# Connections.net
KiCad netlist of a schematic drawn in Altium Designer
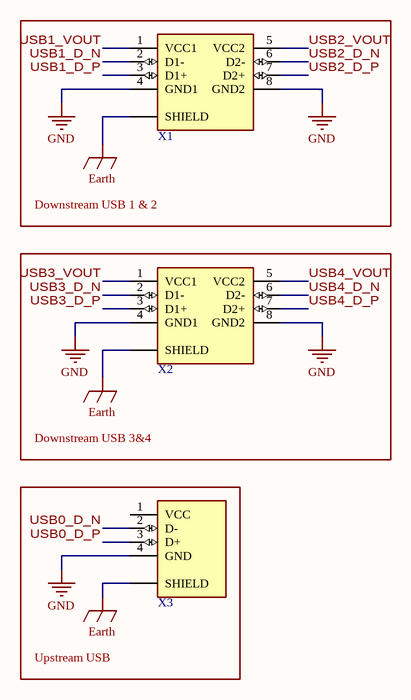
[diagram p0: Connections.SchDoc]

(export (version "E")
  (design (tool "Eeschema 10.0.6"))
  (components
    (comp (ref "X1")
      (value "USB-A")
      (footprint "[USB] Type-A Dual")
      (description "61400826021")
      (libsource (lib "Connectors") (part "[USB] Type-A Dual"))
    )
    (comp (ref "X2")
      (value "USB-A")
      (footprint "[USB] Type-A Dual")
      (description "61400826021")
      (libsource (lib "Connectors") (part "[USB] Type-A Dual"))
    )
    (comp (ref "X3")
      (value "USB-B")
      (footprint "[USB] Type-B")
      (description "USB-B-S-F-B-TH")
      (libsource (lib "Connectors") (part "[USB] Type-B"))
    )
  )
  (nets
    (net (code "1") (name "/USB0_D_N") (class "Default")
      (node (ref "X3") (pin "2") (pinfunction "D-_2") (pintype "bidirectional"))
    )
    (net (code "2") (name "/USB0_D_P") (class "Default")
      (node (ref "X3") (pin "3") (pinfunction "D+_3") (pintype "bidirectional"))
    )
    (net (code "3") (name "/USB1_D_N") (class "Default")
      (node (ref "X1") (pin "2") (pinfunction "D1-_2") (pintype "bidirectional"))
    )
    (net (code "4") (name "/USB1_D_P") (class "Default")
      (node (ref "X1") (pin "3") (pinfunction "D1+_3") (pintype "bidirectional"))
    )
    (net (code "5") (name "/USB1_VOUT") (class "Default")
      (node (ref "X1") (pin "1") (pinfunction "VCC1_1") (pintype "power_in"))
    )
    (net (code "6") (name "/USB2_D_N") (class "Default")
      (node (ref "X1") (pin "6") (pinfunction "D2-_6") (pintype "bidirectional"))
    )
    (net (code "7") (name "/USB2_D_P") (class "Default")
      (node (ref "X1") (pin "7") (pinfunction "D2+_7") (pintype "bidirectional"))
    )
    (net (code "8") (name "/USB2_VOUT") (class "Default")
      (node (ref "X1") (pin "5") (pinfunction "VCC2_5") (pintype "power_in"))
    )
    (net (code "9") (name "/USB3_D_N") (class "Default")
      (node (ref "X2") (pin "2") (pinfunction "D1-_2") (pintype "bidirectional"))
    )
    (net (code "10") (name "/USB3_D_P") (class "Default")
      (node (ref "X2") (pin "3") (pinfunction "D1+_3") (pintype "bidirectional"))
    )
    (net (code "11") (name "/USB3_VOUT") (class "Default")
      (node (ref "X2") (pin "1") (pinfunction "VCC1_1") (pintype "power_in"))
    )
    (net (code "12") (name "/USB4_D_N") (class "Default")
      (node (ref "X2") (pin "6") (pinfunction "D2-_6") (pintype "bidirectional"))
    )
    (net (code "13") (name "/USB4_D_P") (class "Default")
      (node (ref "X2") (pin "7") (pinfunction "D2+_7") (pintype "bidirectional"))
    )
    (net (code "14") (name "/USB4_VOUT") (class "Default")
      (node (ref "X2") (pin "5") (pinfunction "VCC2_5") (pintype "power_in"))
    )
    (net (code "15") (name "Earth") (class "Default")
      (node (ref "X1") (pin "MH") (pinfunction "SHIELD_MH") (pintype "passive"))
      (node (ref "X2") (pin "MH") (pinfunction "SHIELD_MH") (pintype "passive"))
      (node (ref "X3") (pin "MH") (pinfunction "SHIELD_MH") (pintype "passive"))
    )
    (net (code "16") (name "GND") (class "Default")
      (node (ref "X1") (pin "4") (pinfunction "GND1_4") (pintype "power_in"))
      (node (ref "X1") (pin "8") (pinfunction "GND2_8") (pintype "power_in"))
      (node (ref "X2") (pin "4") (pinfunction "GND1_4") (pintype "power_in"))
      (node (ref "X2") (pin "8") (pinfunction "GND2_8") (pintype "power_in"))
      (node (ref "X3") (pin "4") (pinfunction "GND_4") (pintype "power_in"))
    )
    (net (code "17") (name "unconnected-(X3-VCC-Pad1)") (class "Default")
      (node (ref "X3") (pin "1") (pinfunction "VCC_1") (pintype "power_in"))
    )
  )
)
